# Basic.net
KiCad netlist of a schematic drawn in EAGLE
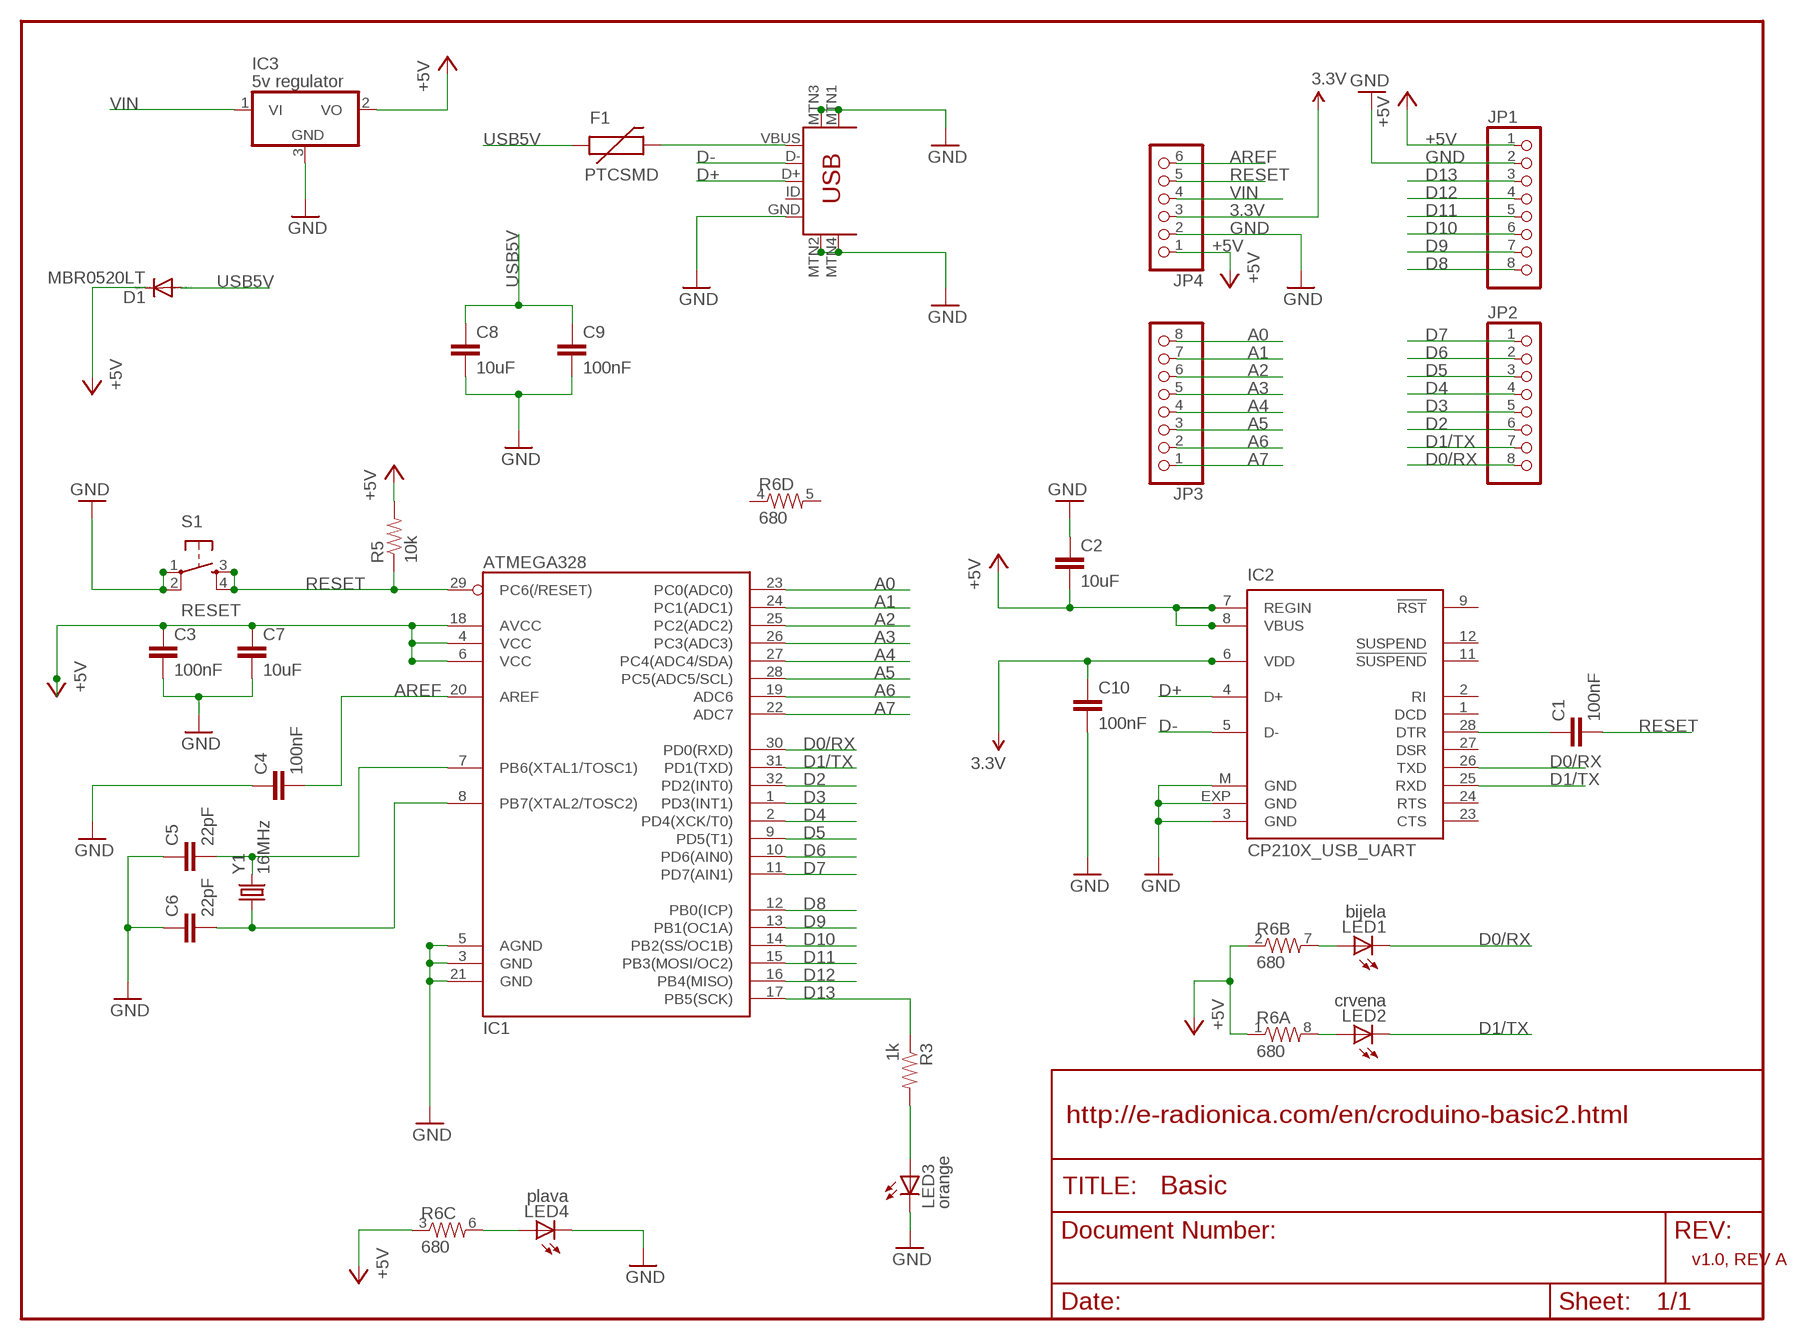
[diagram p0: schematic, sheet 1]

(export (version "E")
  (design (tool "Eeschema 10.0.6"))
  (components
    (comp (ref "C1")
      (value "100nF")
      (footprint "eagle-import:0603-CAP")
      (libsource (lib "eagle-import") (part "CAP0603-CAP"))
    )
    (comp (ref "C2")
      (value "10uF")
      (footprint "eagle-import:C3216")
      (libsource (lib "eagle-import") (part "C-EUC3216"))
    )
    (comp (ref "C3")
      (value "100nF")
      (footprint "eagle-import:0603-CAP")
      (libsource (lib "eagle-import") (part "CAP0603-CAP"))
    )
    (comp (ref "C4")
      (value "100nF")
      (footprint "eagle-import:0603-CAP")
      (libsource (lib "eagle-import") (part "CAP0603-CAP"))
    )
    (comp (ref "C5")
      (value "22pF")
      (footprint "eagle-import:0603-CAP")
      (libsource (lib "eagle-import") (part "CAP0603-CAP"))
    )
    (comp (ref "C6")
      (value "22pF")
      (footprint "eagle-import:0603-CAP")
      (libsource (lib "eagle-import") (part "CAP0603-CAP"))
    )
    (comp (ref "C7")
      (value "10uF")
      (footprint "eagle-import:C3216")
      (libsource (lib "eagle-import") (part "C-EUC3216"))
    )
    (comp (ref "C8")
      (value "10uF")
      (footprint "eagle-import:C3216")
      (libsource (lib "eagle-import") (part "C-EUC3216"))
    )
    (comp (ref "C9")
      (value "100nF")
      (footprint "eagle-import:0603-CAP")
      (libsource (lib "eagle-import") (part "CAP0603-CAP"))
    )
    (comp (ref "C10")
      (value "100nF")
      (footprint "eagle-import:0603-CAP")
      (libsource (lib "eagle-import") (part "CAP0603-CAP"))
    )
    (comp (ref "D1")
      (value "MBR0520LT")
      (footprint "eagle-import:SOD123")
      (libsource (lib "eagle-import") (part "MBR0520LT"))
    )
    (comp (ref "F1")
      (value "PTCSMD")
      (footprint "eagle-import:PTC-1206")
      (libsource (lib "eagle-import") (part "PTCSMD"))
    )
    (comp (ref "IC1")
      (value "ATMEGA328")
      (footprint "eagle-import:TQFP32-08")
      (libsource (lib "eagle-import") (part "ATMEGA168"))
    )
    (comp (ref "IC2")
      (value "CP210X_USB_UART")
      (footprint "eagle-import:MLP28")
      (libsource (lib "eagle-import") (part "CP210X_USB_UART"))
    )
    (comp (ref "IC3")
      (value "5v regulator")
      (footprint "eagle-import:TO252")
      (libsource (lib "eagle-import") (part "78DT05"))
    )
    (comp (ref "JP1")
      (value "PINHD-1X8BIG")
      (footprint "eagle-import:1X08-BIG")
      (libsource (lib "eagle-import") (part "PINHD-1X8BIG"))
    )
    (comp (ref "JP2")
      (value "PINHD-1X8BIG")
      (footprint "eagle-import:1X08-BIG")
      (libsource (lib "eagle-import") (part "PINHD-1X8BIG"))
    )
    (comp (ref "JP3")
      (value "PINHD-1X8BIG")
      (footprint "eagle-import:1X08-BIG")
      (libsource (lib "eagle-import") (part "PINHD-1X8BIG"))
    )
    (comp (ref "JP4")
      (value "PINHD-1X6B")
      (footprint "eagle-import:1X06-BIG")
      (libsource (lib "eagle-import") (part "PINHD-1X6B"))
    )
    (comp (ref "LED1")
      (value "bijela")
      (footprint "eagle-import:CHIP-LED0805")
      (libsource (lib "eagle-import") (part "LEDCHIP-LED0805"))
    )
    (comp (ref "LED2")
      (value "crvena")
      (footprint "eagle-import:CHIP-LED0805")
      (libsource (lib "eagle-import") (part "LEDCHIP-LED0805"))
    )
    (comp (ref "LED3")
      (value "orange")
      (footprint "eagle-import:CHIP-LED0805")
      (libsource (lib "eagle-import") (part "LEDCHIP-LED0805"))
    )
    (comp (ref "LED4")
      (value "plava")
      (footprint "eagle-import:CHIP-LED0805")
      (libsource (lib "eagle-import") (part "LEDCHIP-LED0805"))
    )
    (comp (ref "R3")
      (value "1k")
      (footprint "eagle-import:0603-RES")
      (libsource (lib "eagle-import") (part "RESISTOR0603-RES"))
    )
    (comp (ref "R5")
      (value "10k")
      (footprint "eagle-import:0603-RES")
      (libsource (lib "eagle-import") (part "RESISTOR0603-RES"))
    )
    (comp (ref "R6")
      (value "680")
      (footprint "eagle-import:0603-ARV")
      (libsource (lib "eagle-import") (part "RESISTOR-ARRAY0603-ARV"))
    )
    (comp (ref "S1")
      (value "RESET")
      (footprint "eagle-import:TACTILE_SWITCH_SMD")
      (libsource (lib "eagle-import") (part "TAC_SWITCHSMD"))
    )
    (comp (ref "U1")
      (value "USB-MINIB")
      (footprint "eagle-import:USB-MINIB")
      (libsource (lib "eagle-import") (part "USB-MINIB-5PIN"))
    )
    (comp (ref "Y1")
      (value "16MHz")
      (footprint "eagle-import:CRYSTAL-SMD-5X3")
      (libsource (lib "eagle-import") (part "CRYSTAL5X3"))
    )
  )
  (nets
    (net (code "1") (name "+5V") (class "Default")
      (node (ref "C2") (pin "2") (pinfunction "2_2") (pintype "passive"))
      (node (ref "C3") (pin "1") (pinfunction "1_1") (pintype "passive"))
      (node (ref "C7") (pin "1") (pinfunction "1_1") (pintype "passive"))
      (node (ref "D1") (pin "C") (pinfunction "C_C") (pintype "passive"))
      (node (ref "IC1") (pin "18") (pinfunction "AVCC_18") (pintype "bidirectional"))
      (node (ref "IC1") (pin "4") (pinfunction "VCC_4") (pintype "bidirectional"))
      (node (ref "IC1") (pin "6") (pinfunction "VCC_6") (pintype "bidirectional"))
      (node (ref "IC2") (pin "7") (pinfunction "REGIN_7") (pintype "passive"))
      (node (ref "IC2") (pin "8") (pinfunction "VBUS_8") (pintype "input"))
      (node (ref "IC3") (pin "2") (pinfunction "VO_2") (pintype "passive"))
      (node (ref "JP1") (pin "1") (pinfunction "1_1") (pintype "passive"))
      (node (ref "JP4") (pin "1") (pinfunction "1_1") (pintype "passive"))
      (node (ref "R5") (pin "2") (pinfunction "2_2") (pintype "passive"))
      (node (ref "R6") (pin "1") (pinfunction "1_1") (pintype "passive"))
      (node (ref "R6") (pin "2") (pinfunction "1_2") (pintype "passive"))
      (node (ref "R6") (pin "3") (pinfunction "1_3") (pintype "passive"))
    )
    (net (code "2") (name "/A0") (class "Default")
      (node (ref "IC1") (pin "23") (pinfunction "PC0(ADC0)_23") (pintype "bidirectional"))
      (node (ref "JP3") (pin "8") (pinfunction "8_8") (pintype "passive"))
    )
    (net (code "3") (name "/A1") (class "Default")
      (node (ref "IC1") (pin "24") (pinfunction "PC1(ADC1)_24") (pintype "bidirectional"))
      (node (ref "JP3") (pin "7") (pinfunction "7_7") (pintype "passive"))
    )
    (net (code "4") (name "/A2") (class "Default")
      (node (ref "IC1") (pin "25") (pinfunction "PC2(ADC2)_25") (pintype "bidirectional"))
      (node (ref "JP3") (pin "6") (pinfunction "6_6") (pintype "passive"))
    )
    (net (code "5") (name "/A3") (class "Default")
      (node (ref "IC1") (pin "26") (pinfunction "PC3(ADC3)_26") (pintype "bidirectional"))
      (node (ref "JP3") (pin "5") (pinfunction "5_5") (pintype "passive"))
    )
    (net (code "6") (name "/A4") (class "Default")
      (node (ref "IC1") (pin "27") (pinfunction "PC4(ADC4/SDA)_27") (pintype "bidirectional"))
      (node (ref "JP3") (pin "4") (pinfunction "4_4") (pintype "passive"))
    )
    (net (code "7") (name "/A5") (class "Default")
      (node (ref "IC1") (pin "28") (pinfunction "PC5(ADC5/SCL)_28") (pintype "bidirectional"))
      (node (ref "JP3") (pin "3") (pinfunction "3_3") (pintype "passive"))
    )
    (net (code "8") (name "/A6") (class "Default")
      (node (ref "IC1") (pin "19") (pinfunction "ADC6_19") (pintype "bidirectional"))
      (node (ref "JP3") (pin "2") (pinfunction "2_2") (pintype "passive"))
    )
    (net (code "9") (name "/A7") (class "Default")
      (node (ref "IC1") (pin "22") (pinfunction "ADC7_22") (pintype "bidirectional"))
      (node (ref "JP3") (pin "1") (pinfunction "1_1") (pintype "passive"))
    )
    (net (code "10") (name "/AREF") (class "Default")
      (node (ref "C4") (pin "2") (pinfunction "2_2") (pintype "passive"))
      (node (ref "IC1") (pin "20") (pinfunction "AREF_20") (pintype "bidirectional"))
      (node (ref "JP4") (pin "6") (pinfunction "6_6") (pintype "passive"))
    )
    (net (code "11") (name "/D+") (class "Default")
      (node (ref "IC2") (pin "4") (pinfunction "D+_4") (pintype "bidirectional"))
      (node (ref "U1") (pin "D+") (pinfunction "D+_D+") (pintype "bidirectional"))
    )
    (net (code "12") (name "/D-") (class "Default")
      (node (ref "IC2") (pin "5") (pinfunction "D-_5") (pintype "bidirectional"))
      (node (ref "U1") (pin "D-") (pinfunction "D-_D-") (pintype "bidirectional"))
    )
    (net (code "13") (name "/D0{slash}RX") (class "Default")
      (node (ref "IC1") (pin "30") (pinfunction "PD0(RXD)_30") (pintype "bidirectional"))
      (node (ref "IC2") (pin "26") (pinfunction "TXD_26") (pintype "output"))
      (node (ref "JP2") (pin "8") (pinfunction "8_8") (pintype "passive"))
      (node (ref "LED1") (pin "C") (pinfunction "C_C") (pintype "passive"))
    )
    (net (code "14") (name "/D1{slash}TX") (class "Default")
      (node (ref "IC1") (pin "31") (pinfunction "PD1(TXD)_31") (pintype "bidirectional"))
      (node (ref "IC2") (pin "25") (pinfunction "RXD_25") (pintype "input"))
      (node (ref "JP2") (pin "7") (pinfunction "7_7") (pintype "passive"))
      (node (ref "LED2") (pin "C") (pinfunction "C_C") (pintype "passive"))
    )
    (net (code "15") (name "/D2") (class "Default")
      (node (ref "IC1") (pin "32") (pinfunction "PD2(INT0)_32") (pintype "bidirectional"))
      (node (ref "JP2") (pin "6") (pinfunction "6_6") (pintype "passive"))
    )
    (net (code "16") (name "/D3") (class "Default")
      (node (ref "IC1") (pin "1") (pinfunction "PD3(INT1)_1") (pintype "bidirectional"))
      (node (ref "JP2") (pin "5") (pinfunction "5_5") (pintype "passive"))
    )
    (net (code "17") (name "/D4") (class "Default")
      (node (ref "IC1") (pin "2") (pinfunction "PD4(XCK/T0)_2") (pintype "bidirectional"))
      (node (ref "JP2") (pin "4") (pinfunction "4_4") (pintype "passive"))
    )
    (net (code "18") (name "/D5") (class "Default")
      (node (ref "IC1") (pin "9") (pinfunction "PD5(T1)_9") (pintype "bidirectional"))
      (node (ref "JP2") (pin "3") (pinfunction "3_3") (pintype "passive"))
    )
    (net (code "19") (name "/D6") (class "Default")
      (node (ref "IC1") (pin "10") (pinfunction "PD6(AIN0)_10") (pintype "bidirectional"))
      (node (ref "JP2") (pin "2") (pinfunction "2_2") (pintype "passive"))
    )
    (net (code "20") (name "/D7") (class "Default")
      (node (ref "IC1") (pin "11") (pinfunction "PD7(AIN1)_11") (pintype "bidirectional"))
      (node (ref "JP2") (pin "1") (pinfunction "1_1") (pintype "passive"))
    )
    (net (code "21") (name "/D8") (class "Default")
      (node (ref "IC1") (pin "12") (pinfunction "PB0(ICP)_12") (pintype "bidirectional"))
      (node (ref "JP1") (pin "8") (pinfunction "8_8") (pintype "passive"))
    )
    (net (code "22") (name "/D9") (class "Default")
      (node (ref "IC1") (pin "13") (pinfunction "PB1(OC1A)_13") (pintype "bidirectional"))
      (node (ref "JP1") (pin "7") (pinfunction "7_7") (pintype "passive"))
    )
    (net (code "23") (name "/D10") (class "Default")
      (node (ref "IC1") (pin "14") (pinfunction "PB2(SS/OC1B)_14") (pintype "bidirectional"))
      (node (ref "JP1") (pin "6") (pinfunction "6_6") (pintype "passive"))
    )
    (net (code "24") (name "/D11") (class "Default")
      (node (ref "IC1") (pin "15") (pinfunction "PB3(MOSI/OC2)_15") (pintype "bidirectional"))
      (node (ref "JP1") (pin "5") (pinfunction "5_5") (pintype "passive"))
    )
    (net (code "25") (name "/D12") (class "Default")
      (node (ref "IC1") (pin "16") (pinfunction "PB4(MISO)_16") (pintype "bidirectional"))
      (node (ref "JP1") (pin "4") (pinfunction "4_4") (pintype "passive"))
    )
    (net (code "26") (name "/D13") (class "Default")
      (node (ref "IC1") (pin "17") (pinfunction "PB5(SCK)_17") (pintype "bidirectional"))
      (node (ref "JP1") (pin "3") (pinfunction "3_3") (pintype "passive"))
      (node (ref "R3") (pin "1") (pinfunction "1_1") (pintype "passive"))
    )
    (net (code "27") (name "/RESET") (class "Default")
      (node (ref "C1") (pin "2") (pinfunction "2_2") (pintype "passive"))
      (node (ref "IC1") (pin "29") (pinfunction "PC6(/RESET)_29") (pintype "bidirectional"))
      (node (ref "JP4") (pin "5") (pinfunction "5_5") (pintype "passive"))
      (node (ref "R5") (pin "1") (pinfunction "1_1") (pintype "passive"))
      (node (ref "S1") (pin "3") (pinfunction "3_3") (pintype "passive"))
      (node (ref "S1") (pin "4") (pinfunction "4_4") (pintype "passive"))
    )
    (net (code "28") (name "/USB5V") (class "Default")
      (node (ref "C8") (pin "1") (pinfunction "1_1") (pintype "passive"))
      (node (ref "C9") (pin "1") (pinfunction "1_1") (pintype "passive"))
      (node (ref "D1") (pin "A") (pinfunction "A_A") (pintype "passive"))
      (node (ref "F1") (pin "1") (pinfunction "1_1") (pintype "bidirectional"))
    )
    (net (code "29") (name "/VIN") (class "Default")
      (node (ref "IC3") (pin "1") (pinfunction "VI_1") (pintype "input"))
      (node (ref "JP4") (pin "4") (pinfunction "4_4") (pintype "passive"))
    )
    (net (code "30") (name "3.3V") (class "Default")
      (node (ref "C10") (pin "1") (pinfunction "1_1") (pintype "passive"))
      (node (ref "IC2") (pin "6") (pinfunction "VDD_6") (pintype "power_in"))
      (node (ref "JP4") (pin "3") (pinfunction "3_3") (pintype "passive"))
    )
    (net (code "31") (name "GND") (class "Default")
      (node (ref "C10") (pin "2") (pinfunction "2_2") (pintype "passive"))
      (node (ref "C2") (pin "1") (pinfunction "1_1") (pintype "passive"))
      (node (ref "C3") (pin "2") (pinfunction "2_2") (pintype "passive"))
      (node (ref "C4") (pin "1") (pinfunction "1_1") (pintype "passive"))
      (node (ref "C5") (pin "1") (pinfunction "1_1") (pintype "passive"))
      (node (ref "C6") (pin "1") (pinfunction "1_1") (pintype "passive"))
      (node (ref "C7") (pin "2") (pinfunction "2_2") (pintype "passive"))
      (node (ref "C8") (pin "2") (pinfunction "2_2") (pintype "passive"))
      (node (ref "C9") (pin "2") (pinfunction "2_2") (pintype "passive"))
      (node (ref "IC1") (pin "21") (pinfunction "GND_21") (pintype "bidirectional"))
      (node (ref "IC1") (pin "3") (pinfunction "GND_3") (pintype "bidirectional"))
      (node (ref "IC1") (pin "5") (pinfunction "AGND_5") (pintype "bidirectional"))
      (node (ref "IC2") (pin "3") (pinfunction "GND_3") (pintype "power_in"))
      (node (ref "IC2") (pin "EXP") (pinfunction "GND_EXP") (pintype "power_in"))
      (node (ref "IC2") (pin "M") (pinfunction "GND_M") (pintype "power_in"))
      (node (ref "IC3") (pin "3") (pinfunction "GND_3") (pintype "passive"))
      (node (ref "JP1") (pin "2") (pinfunction "2_2") (pintype "passive"))
      (node (ref "JP4") (pin "2") (pinfunction "2_2") (pintype "passive"))
      (node (ref "LED3") (pin "C") (pinfunction "C_C") (pintype "passive"))
      (node (ref "LED4") (pin "C") (pinfunction "C_C") (pintype "passive"))
      (node (ref "S1") (pin "1") (pinfunction "1_1") (pintype "passive"))
      (node (ref "S1") (pin "2") (pinfunction "2_2") (pintype "passive"))
      (node (ref "U1") (pin "GND") (pinfunction "GND_GND") (pintype "bidirectional"))
      (node (ref "U1") (pin "MTN1") (pinfunction "MTN2_MTN1") (pintype "bidirectional"))
      (node (ref "U1") (pin "MTN2") (pinfunction "MTN3_MTN2") (pintype "bidirectional"))
      (node (ref "U1") (pin "MTN3") (pinfunction "MTN1_MTN3") (pintype "bidirectional"))
      (node (ref "U1") (pin "MTN4") (pinfunction "MTN4_MTN4") (pintype "bidirectional"))
    )
    (net (code "32") (name "Net-(F1-Pad2)") (class "Default")
      (node (ref "F1") (pin "2") (pinfunction "2_2") (pintype "bidirectional"))
      (node (ref "U1") (pin "VBUS") (pinfunction "VBUS_VBUS") (pintype "bidirectional"))
    )
    (net (code "33") (name "Net-(IC1-PB6(XTAL1{slash}TOSC1))") (class "Default")
      (node (ref "C5") (pin "2") (pinfunction "2_2") (pintype "passive"))
      (node (ref "IC1") (pin "7") (pinfunction "PB6(XTAL1/TOSC1)_7") (pintype "bidirectional"))
      (node (ref "Y1") (pin "3") (pinfunction "2_3") (pintype "passive"))
    )
    (net (code "34") (name "Net-(IC1-PB7(XTAL2{slash}TOSC2))") (class "Default")
      (node (ref "C6") (pin "2") (pinfunction "2_2") (pintype "passive"))
      (node (ref "IC1") (pin "8") (pinfunction "PB7(XTAL2/TOSC2)_8") (pintype "bidirectional"))
      (node (ref "Y1") (pin "1") (pinfunction "1_1") (pintype "passive"))
    )
    (net (code "35") (name "Net-(IC2-DTR)") (class "Default")
      (node (ref "C1") (pin "1") (pinfunction "1_1") (pintype "passive"))
      (node (ref "IC2") (pin "28") (pinfunction "DTR_28") (pintype "output"))
    )
    (net (code "36") (name "Net-(LED3-PadA)") (class "Default")
      (node (ref "LED3") (pin "A") (pinfunction "A_A") (pintype "passive"))
      (node (ref "R3") (pin "2") (pinfunction "2_2") (pintype "passive"))
    )
    (net (code "37") (name "Net-(R6A-2)") (class "Default")
      (node (ref "LED2") (pin "A") (pinfunction "A_A") (pintype "passive"))
      (node (ref "R6") (pin "8") (pinfunction "2_8") (pintype "passive"))
    )
    (net (code "38") (name "Net-(R6B-2)") (class "Default")
      (node (ref "LED1") (pin "A") (pinfunction "A_A") (pintype "passive"))
      (node (ref "R6") (pin "7") (pinfunction "2_7") (pintype "passive"))
    )
    (net (code "39") (name "Net-(R6C-2)") (class "Default")
      (node (ref "LED4") (pin "A") (pinfunction "A_A") (pintype "passive"))
      (node (ref "R6") (pin "6") (pinfunction "2_6") (pintype "passive"))
    )
    (net (code "40") (name "unconnected-(IC2-CTS-Pad23)") (class "Default")
      (node (ref "IC2") (pin "23") (pinfunction "CTS_23") (pintype "input"))
    )
    (net (code "41") (name "unconnected-(IC2-DCD-Pad1)") (class "Default")
      (node (ref "IC2") (pin "1") (pinfunction "DCD_1") (pintype "input"))
    )
    (net (code "42") (name "unconnected-(IC2-DSR-Pad27)") (class "Default")
      (node (ref "IC2") (pin "27") (pinfunction "DSR_27") (pintype "input"))
    )
    (net (code "43") (name "unconnected-(IC2-RI-Pad2)") (class "Default")
      (node (ref "IC2") (pin "2") (pinfunction "RI_2") (pintype "input"))
    )
    (net (code "44") (name "unconnected-(IC2-RTS-Pad24)") (class "Default")
      (node (ref "IC2") (pin "24") (pinfunction "RTS_24") (pintype "output"))
    )
    (net (code "45") (name "unconnected-(IC2-SUSPEND-Pad12)") (class "Default")
      (node (ref "IC2") (pin "12") (pinfunction "SUSPEND_12") (pintype "output"))
    )
    (net (code "46") (name "unconnected-(IC2-~{RST}-Pad9)") (class "Default")
      (node (ref "IC2") (pin "9") (pinfunction "~{RST}_9") (pintype "bidirectional"))
    )
    (net (code "47") (name "unconnected-(IC2-~{SUSPEND}-Pad11)") (class "Default")
      (node (ref "IC2") (pin "11") (pinfunction "~{SUSPEND}_11") (pintype "output"))
    )
    (net (code "48") (name "unconnected-(R6D-1-Pad4)") (class "Default")
      (node (ref "R6") (pin "4") (pinfunction "1_4") (pintype "passive"))
    )
    (net (code "49") (name "unconnected-(R6D-2-Pad5)") (class "Default")
      (node (ref "R6") (pin "5") (pinfunction "2_5") (pintype "passive"))
    )
    (net (code "50") (name "unconnected-(U1-PadID)") (class "Default")
      (node (ref "U1") (pin "ID") (pinfunction "ID_ID") (pintype "bidirectional"))
    )
  )
)
